# SCH_NIRV2_Driver_2022-05-05.net
KiCad netlist of a schematic drawn in EasyEDA
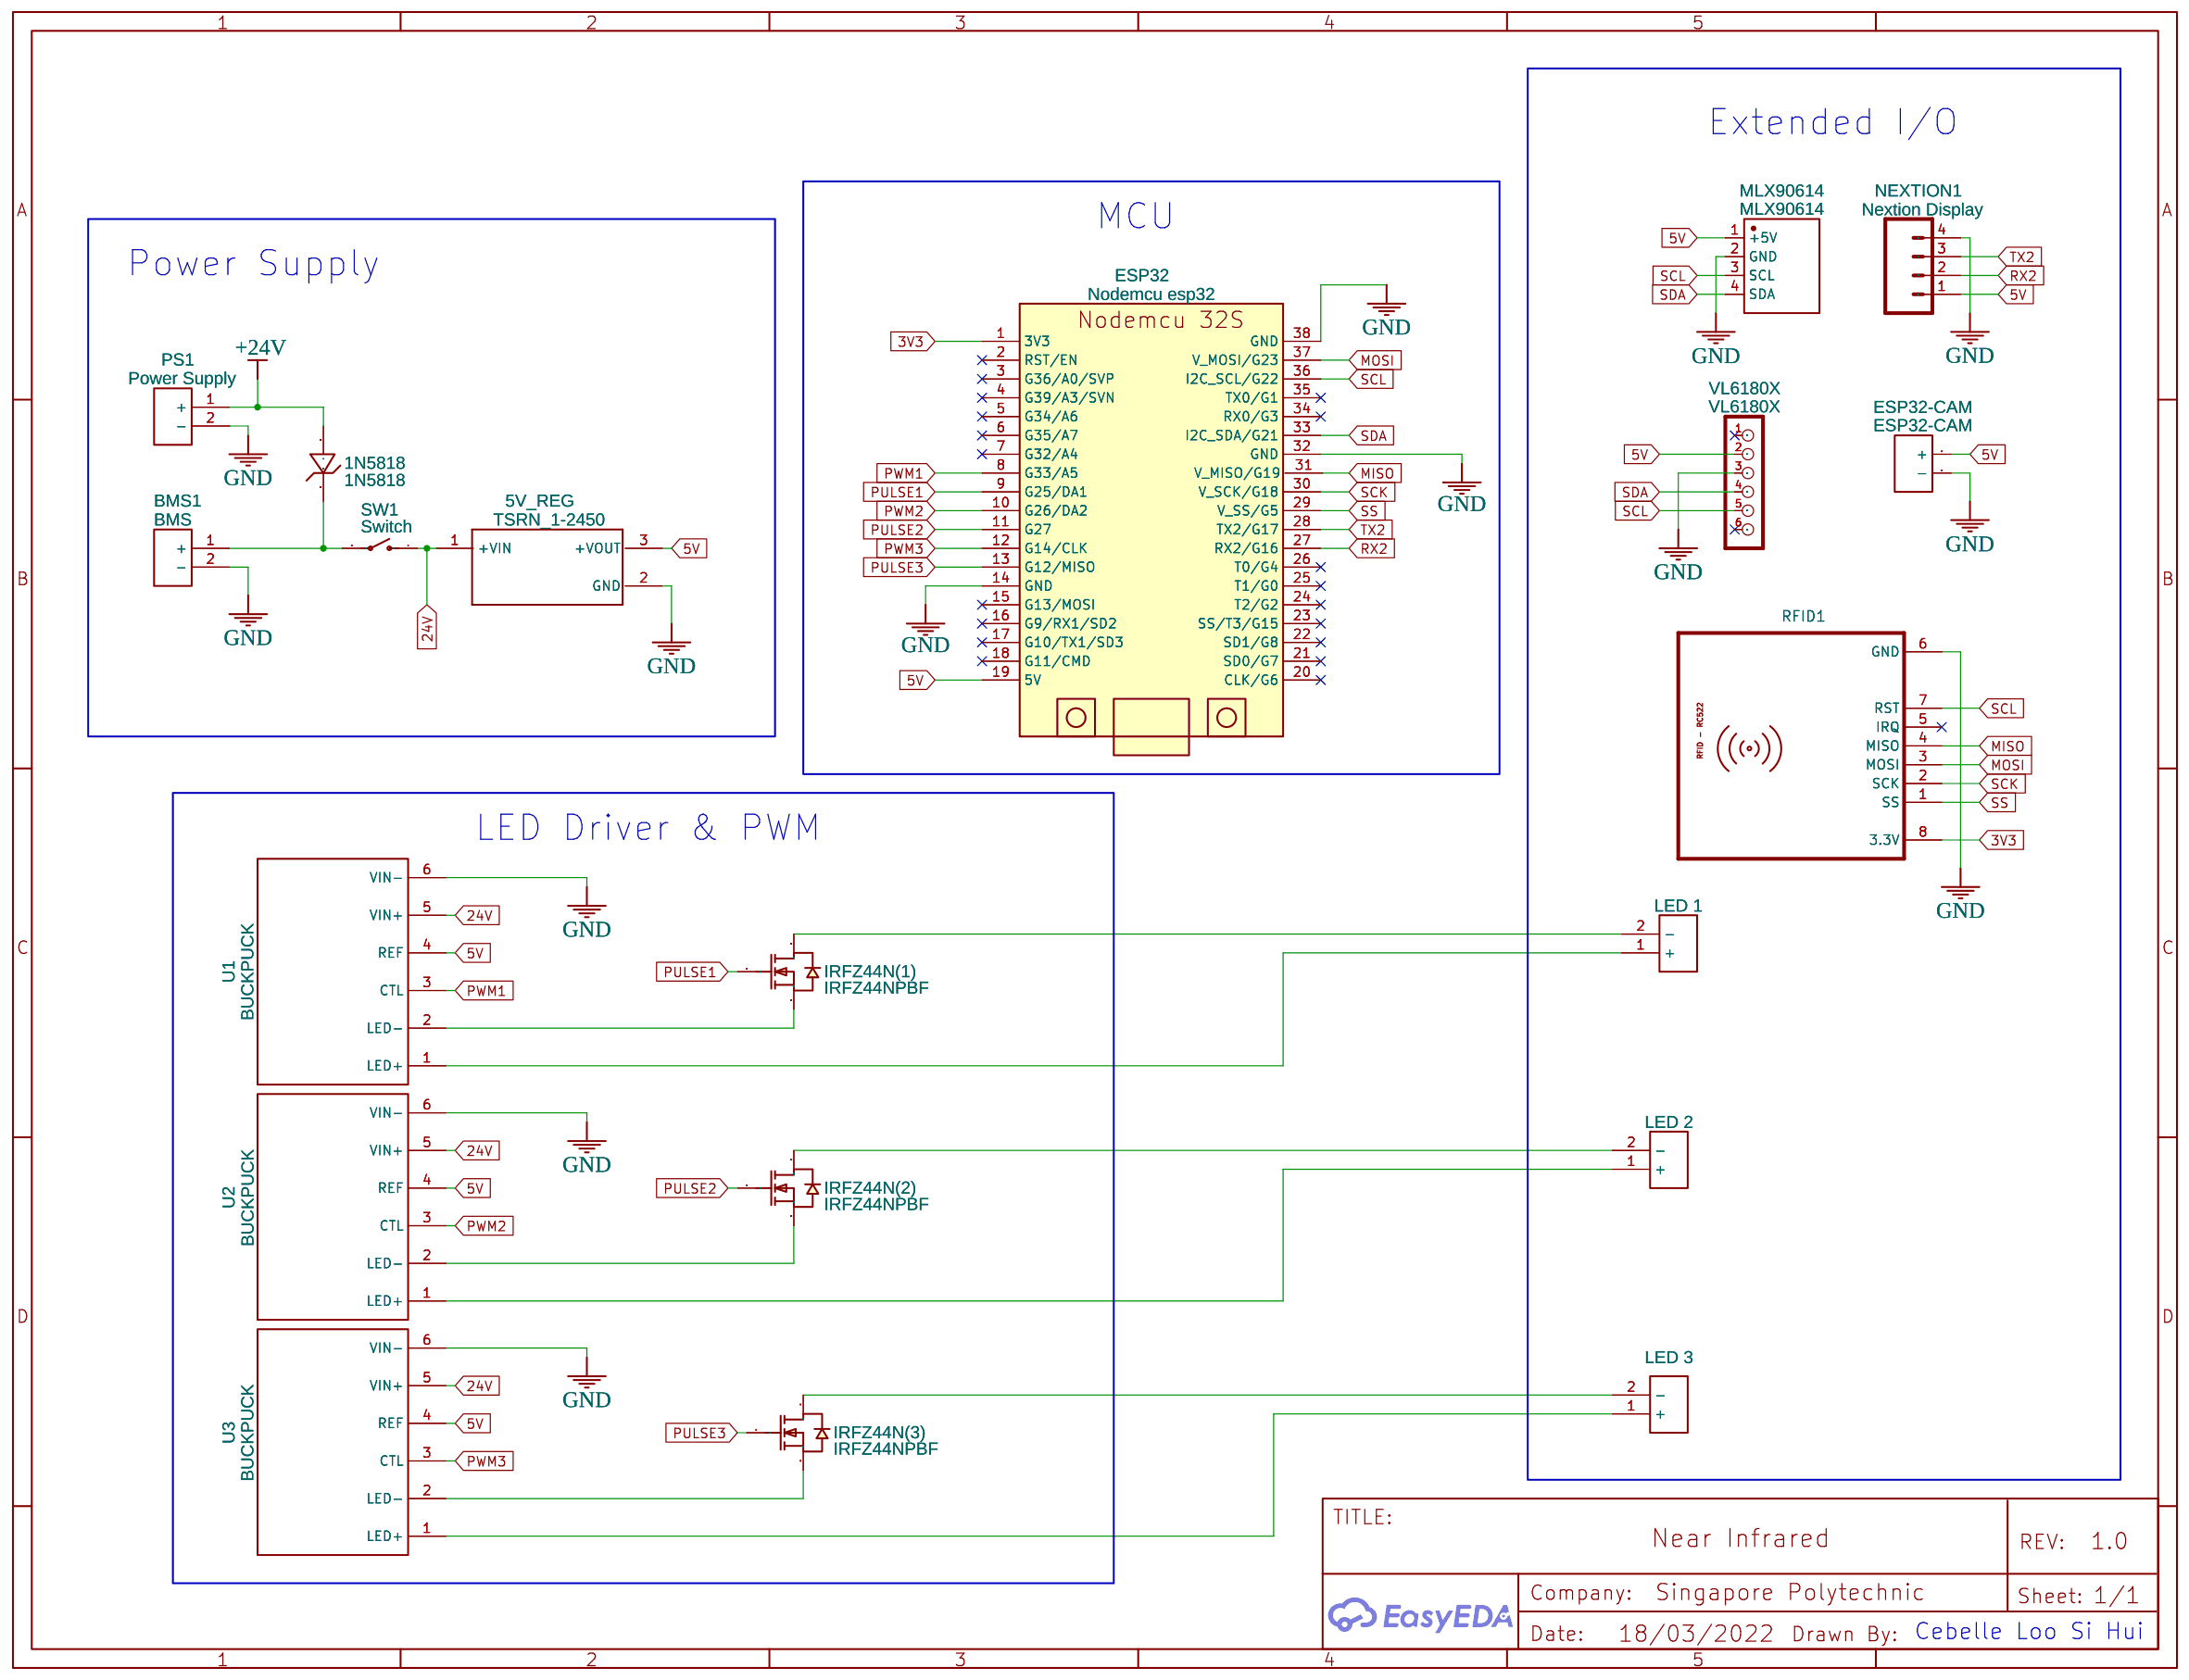
[diagram p0: schematic sheet]

(export (version "E")
  (design (tool "Eeschema 10.0.6"))
  (components
    (comp (ref "1N5818")
      (value "1N5818")
      (fields (field (name "BOM_Supplier Part") "C402217"))
      (libsource (lib "") (part "1N5818"))
    )
    (comp (ref "5V_REG") (value "TSRN_1-2450") (libsource (lib "") (part "TSRN_1-2450")))
    (comp (ref "BMS1")
      (value "BMS")
      (fields
        (field (name "BOM_Manufacturer Part") "WJ103-5.00-2P")
        (field (name "BOM_Supplier Part") "C8439")
      )
      (libsource (lib "") (part "WJ103-5.00-2P_1"))
    )
    (comp (ref "ESP32") (value "Nodemcu esp32") (libsource (lib "") (part "Nodemcu esp32")))
    (comp (ref "ESP32-CAM")
      (value "ESP32-CAM")
      (fields
        (field (name "BOM_Manufacturer Part") "2.54-1*2PFemale")
        (field (name "BOM_Supplier Part") "C49661")
      )
      (libsource (lib "") (part "Header-Female-2.54_1x2"))
    )
    (comp (ref "IRFZ44N(1)")
      (value "IRFZ44NPBF")
      (fields (field (name "BOM_Supplier Part") "C2586"))
      (libsource (lib "") (part "IRFZ44NPBF_2"))
    )
    (comp (ref "IRFZ44N(2)")
      (value "IRFZ44NPBF")
      (fields (field (name "BOM_Supplier Part") "C2586"))
      (libsource (lib "") (part "IRFZ44NPBF"))
    )
    (comp (ref "IRFZ44N(3)")
      (value "IRFZ44NPBF")
      (fields (field (name "BOM_Supplier Part") "C2586"))
      (libsource (lib "") (part "IRFZ44NPBF_1"))
    )
    (comp (ref "LED1")
      (value "LED 1")
      (fields
        (field (name "BOM_Manufacturer Part") "WJ103-5.00-2P")
        (field (name "BOM_Supplier Part") "C8439")
      )
      (libsource (lib "") (part "WJ103-5.00-2P"))
    )
    (comp (ref "LED2")
      (value "LED 2")
      (fields
        (field (name "BOM_Manufacturer Part") "WJ103-5.00-2P")
        (field (name "BOM_Supplier Part") "C8439")
      )
      (libsource (lib "") (part "WJ103-5.00-2P"))
    )
    (comp (ref "LED3")
      (value "LED 3")
      (fields
        (field (name "BOM_Manufacturer Part") "WJ103-5.00-2P")
        (field (name "BOM_Supplier Part") "C8439")
      )
      (libsource (lib "") (part "WJ103-5.00-2P"))
    )
    (comp (ref "MLX90614")
      (value "MLX90614")
      (fields
        (field (name "BOM_Manufacturer Part") "RE-H042TD-1190(LF)(SN)")
        (field (name "BOM_Supplier Part") "C265319")
      )
      (libsource (lib "") (part "RE-H042TD-1190(LF)(SN)"))
    )
    (comp (ref "NEXTION1") (value "Nextion Display") (libsource (lib "") (part "M04POLAR")))
    (comp (ref "PS1")
      (value "Power Supply")
      (fields
        (field (name "BOM_Manufacturer Part") "WJ103-5.00-2P")
        (field (name "BOM_Supplier Part") "C8439")
      )
      (libsource (lib "") (part "WJ103-5.00-2P_2"))
    )
    (comp (ref "RFID1") (value "NO") (libsource (lib "") (part "Unknown_954_-490")))
    (comp (ref "SW1")
      (value "Switch")
      (fields (field (name "BOM_Manufacturer Part") "KCD1-11-1.5x1cm"))
      (libsource (lib "") (part "SWITCH-2P-SPST-Rocker-10x15mm"))
    )
    (comp (ref "U1") (value "BUCKPUCK") (libsource (lib "") (part "BUCKPUCK")))
    (comp (ref "U2") (value "BUCKPUCK") (libsource (lib "") (part "BUCKPUCK")))
    (comp (ref "U3") (value "BUCKPUCK") (libsource (lib "") (part "BUCKPUCK")))
    (comp (ref "VL6180X") (value "VL6180X") (libsource (lib "") (part "CON_HEADER_1X06-PTH")))
  )
  (nets
    (net (code "1") (name "+24V") (class "Default")
      (node (ref "1N5818") (pin "2") (pinfunction "A_2") (pintype "unspecified"))
      (node (ref "PS1") (pin "1") (pinfunction "+_1") (pintype "unspecified"))
    )
    (net (code "2") (name "3V3") (class "Default")
      (node (ref "ESP32") (pin "1") (pinfunction "3V3_1") (pintype "passive"))
      (node (ref "RFID1") (pin "8") (pinfunction "3.3V_8") (pintype "unspecified"))
    )
    (net (code "3") (name "5V") (class "Default")
      (node (ref "5V_REG") (pin "3") (pinfunction "+VOUT_3") (pintype "bidirectional"))
      (node (ref "ESP32") (pin "19") (pinfunction "5V_19") (pintype "passive"))
      (node (ref "ESP32-CAM") (pin "2") (pinfunction "+_2") (pintype "input"))
      (node (ref "MLX90614") (pin "1") (pinfunction "+5V_1") (pintype "unspecified"))
      (node (ref "NEXTION1") (pin "1") (pinfunction "GND_1") (pintype "unspecified"))
      (node (ref "U1") (pin "4") (pinfunction "REF_4") (pintype "unspecified"))
      (node (ref "U2") (pin "4") (pinfunction "REF_4") (pintype "unspecified"))
      (node (ref "U3") (pin "4") (pinfunction "REF_4") (pintype "unspecified"))
      (node (ref "VL6180X") (pin "2") (pinfunction "VIN_2") (pintype "unspecified"))
    )
    (net (code "4") (name "24V") (class "Default")
      (node (ref "5V_REG") (pin "1") (pinfunction "+VIN_1") (pintype "bidirectional"))
      (node (ref "SW1") (pin "1") (pinfunction "O_1") (pintype "unspecified"))
      (node (ref "U1") (pin "5") (pinfunction "VIN+_5") (pintype "unspecified"))
      (node (ref "U2") (pin "5") (pinfunction "VIN+_5") (pintype "unspecified"))
      (node (ref "U3") (pin "5") (pinfunction "VIN+_5") (pintype "unspecified"))
    )
    (net (code "5") (name "GND") (class "Default")
      (node (ref "5V_REG") (pin "2") (pinfunction "GND_2") (pintype "bidirectional"))
      (node (ref "BMS1") (pin "2") (pinfunction "-_2") (pintype "unspecified"))
      (node (ref "ESP32") (pin "14") (pinfunction "GND_14") (pintype "passive"))
      (node (ref "ESP32") (pin "32") (pinfunction "GND_32") (pintype "passive"))
      (node (ref "ESP32") (pin "38") (pinfunction "GND_38") (pintype "passive"))
      (node (ref "ESP32-CAM") (pin "1") (pinfunction "-_1") (pintype "input"))
      (node (ref "MLX90614") (pin "2") (pinfunction "GND_2") (pintype "unspecified"))
      (node (ref "NEXTION1") (pin "4") (pinfunction "+5V_4") (pintype "unspecified"))
      (node (ref "PS1") (pin "2") (pinfunction "-_2") (pintype "unspecified"))
      (node (ref "RFID1") (pin "6") (pinfunction "GND_6") (pintype "unspecified"))
      (node (ref "U1") (pin "6") (pinfunction "VIN-_6") (pintype "unspecified"))
      (node (ref "U2") (pin "6") (pinfunction "VIN-_6") (pintype "unspecified"))
      (node (ref "U3") (pin "6") (pinfunction "VIN-_6") (pintype "unspecified"))
      (node (ref "VL6180X") (pin "3") (pinfunction "GND_3") (pintype "unspecified"))
    )
    (net (code "6") (name "MISO") (class "Default")
      (node (ref "ESP32") (pin "31") (pinfunction "V_MISO/G19_31") (pintype "bidirectional"))
      (node (ref "RFID1") (pin "4") (pinfunction "MISO_4") (pintype "unspecified"))
    )
    (net (code "7") (name "MOSI") (class "Default")
      (node (ref "ESP32") (pin "37") (pinfunction "V_MOSI/G23_37") (pintype "bidirectional"))
      (node (ref "RFID1") (pin "3") (pinfunction "MOSI_3") (pintype "unspecified"))
    )
    (net (code "8") (name "Net-(1N5818-C)") (class "Default")
      (node (ref "1N5818") (pin "1") (pinfunction "C_1") (pintype "unspecified"))
      (node (ref "BMS1") (pin "1") (pinfunction "+_1") (pintype "unspecified"))
      (node (ref "SW1") (pin "2") (pinfunction "P_2") (pintype "unspecified"))
    )
    (net (code "9") (name "Net-(IRFZ44N(1)-D)") (class "Default")
      (node (ref "IRFZ44N(1)") (pin "2") (pinfunction "D_2") (pintype "unspecified"))
      (node (ref "LED1") (pin "2") (pinfunction "-_2") (pintype "unspecified"))
    )
    (net (code "10") (name "Net-(IRFZ44N(1)-S)") (class "Default")
      (node (ref "IRFZ44N(1)") (pin "3") (pinfunction "S_3") (pintype "unspecified"))
      (node (ref "U1") (pin "2") (pinfunction "LED-_2") (pintype "unspecified"))
    )
    (net (code "11") (name "Net-(IRFZ44N(2)-D)") (class "Default")
      (node (ref "IRFZ44N(2)") (pin "2") (pinfunction "D_2") (pintype "unspecified"))
      (node (ref "LED2") (pin "2") (pinfunction "-_2") (pintype "unspecified"))
    )
    (net (code "12") (name "Net-(IRFZ44N(2)-S)") (class "Default")
      (node (ref "IRFZ44N(2)") (pin "3") (pinfunction "S_3") (pintype "unspecified"))
      (node (ref "U2") (pin "2") (pinfunction "LED-_2") (pintype "unspecified"))
    )
    (net (code "13") (name "Net-(IRFZ44N(3)-D)") (class "Default")
      (node (ref "IRFZ44N(3)") (pin "2") (pinfunction "D_2") (pintype "unspecified"))
      (node (ref "LED3") (pin "2") (pinfunction "-_2") (pintype "unspecified"))
    )
    (net (code "14") (name "Net-(IRFZ44N(3)-S)") (class "Default")
      (node (ref "IRFZ44N(3)") (pin "3") (pinfunction "S_3") (pintype "unspecified"))
      (node (ref "U3") (pin "2") (pinfunction "LED-_2") (pintype "unspecified"))
    )
    (net (code "15") (name "Net-(LED1-+)") (class "Default")
      (node (ref "LED1") (pin "1") (pinfunction "+_1") (pintype "unspecified"))
      (node (ref "U1") (pin "1") (pinfunction "LED+_1") (pintype "unspecified"))
    )
    (net (code "16") (name "Net-(LED2-+)") (class "Default")
      (node (ref "LED2") (pin "1") (pinfunction "+_1") (pintype "unspecified"))
      (node (ref "U2") (pin "1") (pinfunction "LED+_1") (pintype "unspecified"))
    )
    (net (code "17") (name "Net-(LED3-+)") (class "Default")
      (node (ref "LED3") (pin "1") (pinfunction "+_1") (pintype "unspecified"))
      (node (ref "U3") (pin "1") (pinfunction "LED+_1") (pintype "unspecified"))
    )
    (net (code "18") (name "PULSE1") (class "Default")
      (node (ref "ESP32") (pin "9") (pinfunction "G25/DA1_9") (pintype "bidirectional"))
      (node (ref "IRFZ44N(1)") (pin "1") (pinfunction "G_1") (pintype "unspecified"))
    )
    (net (code "19") (name "PULSE2") (class "Default")
      (node (ref "ESP32") (pin "11") (pinfunction "G27_11") (pintype "bidirectional"))
      (node (ref "IRFZ44N(2)") (pin "1") (pinfunction "G_1") (pintype "unspecified"))
    )
    (net (code "20") (name "PULSE3") (class "Default")
      (node (ref "ESP32") (pin "13") (pinfunction "G12/MISO_13") (pintype "bidirectional"))
      (node (ref "IRFZ44N(3)") (pin "1") (pinfunction "G_1") (pintype "unspecified"))
    )
    (net (code "21") (name "PWM1") (class "Default")
      (node (ref "ESP32") (pin "8") (pinfunction "G33/A5_8") (pintype "bidirectional"))
      (node (ref "U1") (pin "3") (pinfunction "CTL_3") (pintype "unspecified"))
    )
    (net (code "22") (name "PWM2") (class "Default")
      (node (ref "ESP32") (pin "10") (pinfunction "G26/DA2_10") (pintype "bidirectional"))
      (node (ref "U2") (pin "3") (pinfunction "CTL_3") (pintype "unspecified"))
    )
    (net (code "23") (name "PWM3") (class "Default")
      (node (ref "ESP32") (pin "12") (pinfunction "G14/CLK_12") (pintype "bidirectional"))
      (node (ref "U3") (pin "3") (pinfunction "CTL_3") (pintype "unspecified"))
    )
    (net (code "24") (name "RX2") (class "Default")
      (node (ref "ESP32") (pin "27") (pinfunction "RX2/G16_27") (pintype "bidirectional"))
      (node (ref "NEXTION1") (pin "2") (pinfunction "RX_2") (pintype "unspecified"))
    )
    (net (code "25") (name "SCK") (class "Default")
      (node (ref "ESP32") (pin "30") (pinfunction "V_SCK/G18_30") (pintype "bidirectional"))
      (node (ref "RFID1") (pin "2") (pinfunction "SCK_2") (pintype "unspecified"))
    )
    (net (code "26") (name "SCL") (class "Default")
      (node (ref "ESP32") (pin "36") (pinfunction "I2C_SCL/G22_36") (pintype "bidirectional"))
      (node (ref "MLX90614") (pin "3") (pinfunction "SCL_3") (pintype "unspecified"))
      (node (ref "RFID1") (pin "7") (pinfunction "RST_7") (pintype "unspecified"))
      (node (ref "VL6180X") (pin "5") (pinfunction "SCL_5") (pintype "unspecified"))
    )
    (net (code "27") (name "SDA") (class "Default")
      (node (ref "ESP32") (pin "33") (pinfunction "I2C_SDA/G21_33") (pintype "bidirectional"))
      (node (ref "MLX90614") (pin "4") (pinfunction "SDA_4") (pintype "unspecified"))
      (node (ref "VL6180X") (pin "4") (pinfunction "SDA_4") (pintype "unspecified"))
    )
    (net (code "28") (name "SS") (class "Default")
      (node (ref "ESP32") (pin "29") (pinfunction "V_SS/G5_29") (pintype "bidirectional"))
      (node (ref "RFID1") (pin "1") (pinfunction "SS_1") (pintype "unspecified"))
    )
    (net (code "29") (name "TX2") (class "Default")
      (node (ref "ESP32") (pin "28") (pinfunction "TX2/G17_28") (pintype "bidirectional"))
      (node (ref "NEXTION1") (pin "3") (pinfunction "TX_3") (pintype "unspecified"))
    )
    (net (code "30") (name "unconnected-(ESP32-CLK{slash}G6-Pad20)") (class "Default")
      (node (ref "ESP32") (pin "20") (pinfunction "CLK/G6_20") (pintype "bidirectional+no_connect"))
    )
    (net (code "31") (name "unconnected-(ESP32-G9{slash}RX1{slash}SD2-Pad16)") (class "Default")
      (node (ref "ESP32") (pin "16") (pinfunction "G9/RX1/SD2_16") (pintype "bidirectional+no_connect"))
    )
    (net (code "32") (name "unconnected-(ESP32-G10{slash}TX1{slash}SD3-Pad17)") (class "Default")
      (node (ref "ESP32") (pin "17") (pinfunction "G10/TX1/SD3_17") (pintype "bidirectional+no_connect"))
    )
    (net (code "33") (name "unconnected-(ESP32-G11{slash}CMD-Pad18)") (class "Default")
      (node (ref "ESP32") (pin "18") (pinfunction "G11/CMD_18") (pintype "bidirectional+no_connect"))
    )
    (net (code "34") (name "unconnected-(ESP32-G13{slash}MOSI-Pad15)") (class "Default")
      (node (ref "ESP32") (pin "15") (pinfunction "G13/MOSI_15") (pintype "bidirectional+no_connect"))
    )
    (net (code "35") (name "unconnected-(ESP32-G32{slash}A4-Pad7)") (class "Default")
      (node (ref "ESP32") (pin "7") (pinfunction "G32/A4_7") (pintype "bidirectional+no_connect"))
    )
    (net (code "36") (name "unconnected-(ESP32-G34{slash}A6-Pad5)") (class "Default")
      (node (ref "ESP32") (pin "5") (pinfunction "G34/A6_5") (pintype "bidirectional+no_connect"))
    )
    (net (code "37") (name "unconnected-(ESP32-G35{slash}A7-Pad6)") (class "Default")
      (node (ref "ESP32") (pin "6") (pinfunction "G35/A7_6") (pintype "bidirectional+no_connect"))
    )
    (net (code "38") (name "unconnected-(ESP32-G36{slash}A0{slash}SVP-Pad3)") (class "Default")
      (node (ref "ESP32") (pin "3") (pinfunction "G36/A0/SVP_3") (pintype "bidirectional+no_connect"))
    )
    (net (code "39") (name "unconnected-(ESP32-G39{slash}A3{slash}SVN-Pad4)") (class "Default")
      (node (ref "ESP32") (pin "4") (pinfunction "G39/A3/SVN_4") (pintype "bidirectional+no_connect"))
    )
    (net (code "40") (name "unconnected-(ESP32-RST{slash}EN-Pad2)") (class "Default")
      (node (ref "ESP32") (pin "2") (pinfunction "RST/EN_2") (pintype "bidirectional+no_connect"))
    )
    (net (code "41") (name "unconnected-(ESP32-RX0{slash}G3-Pad34)") (class "Default")
      (node (ref "ESP32") (pin "34") (pinfunction "RX0/G3_34") (pintype "bidirectional+no_connect"))
    )
    (net (code "42") (name "unconnected-(ESP32-SD0{slash}G7-Pad21)") (class "Default")
      (node (ref "ESP32") (pin "21") (pinfunction "SD0/G7_21") (pintype "bidirectional+no_connect"))
    )
    (net (code "43") (name "unconnected-(ESP32-SD1{slash}G8-Pad22)") (class "Default")
      (node (ref "ESP32") (pin "22") (pinfunction "SD1/G8_22") (pintype "bidirectional+no_connect"))
    )
    (net (code "44") (name "unconnected-(ESP32-SS{slash}T3{slash}G15-Pad23)") (class "Default")
      (node (ref "ESP32") (pin "23") (pinfunction "SS/T3/G15_23") (pintype "bidirectional+no_connect"))
    )
    (net (code "45") (name "unconnected-(ESP32-T0{slash}G4-Pad26)") (class "Default")
      (node (ref "ESP32") (pin "26") (pinfunction "T0/G4_26") (pintype "bidirectional+no_connect"))
    )
    (net (code "46") (name "unconnected-(ESP32-T1{slash}G0-Pad25)") (class "Default")
      (node (ref "ESP32") (pin "25") (pinfunction "T1/G0_25") (pintype "bidirectional+no_connect"))
    )
    (net (code "47") (name "unconnected-(ESP32-T2{slash}G2-Pad24)") (class "Default")
      (node (ref "ESP32") (pin "24") (pinfunction "T2/G2_24") (pintype "bidirectional+no_connect"))
    )
    (net (code "48") (name "unconnected-(ESP32-TX0{slash}G1-Pad35)") (class "Default")
      (node (ref "ESP32") (pin "35") (pinfunction "TX0/G1_35") (pintype "bidirectional+no_connect"))
    )
    (net (code "49") (name "unconnected-(RFID1-IRQ-Pad5)") (class "Default")
      (node (ref "RFID1") (pin "5") (pinfunction "IRQ_5") (pintype "unspecified+no_connect"))
    )
    (net (code "50") (name "unconnected-(VL6180X-IO1-Pad6)") (class "Default")
      (node (ref "VL6180X") (pin "6") (pinfunction "IO1_6") (pintype "unspecified+no_connect"))
    )
    (net (code "51") (name "unconnected-(VL6180X-VDD-Pad1)") (class "Default")
      (node (ref "VL6180X") (pin "1") (pinfunction "VDD_1") (pintype "unspecified+no_connect"))
    )
  )
)
